# ProProject_20240809-UR5__2024-08-29.net
KiCad netlist of a schematic drawn in EasyEDA Pro
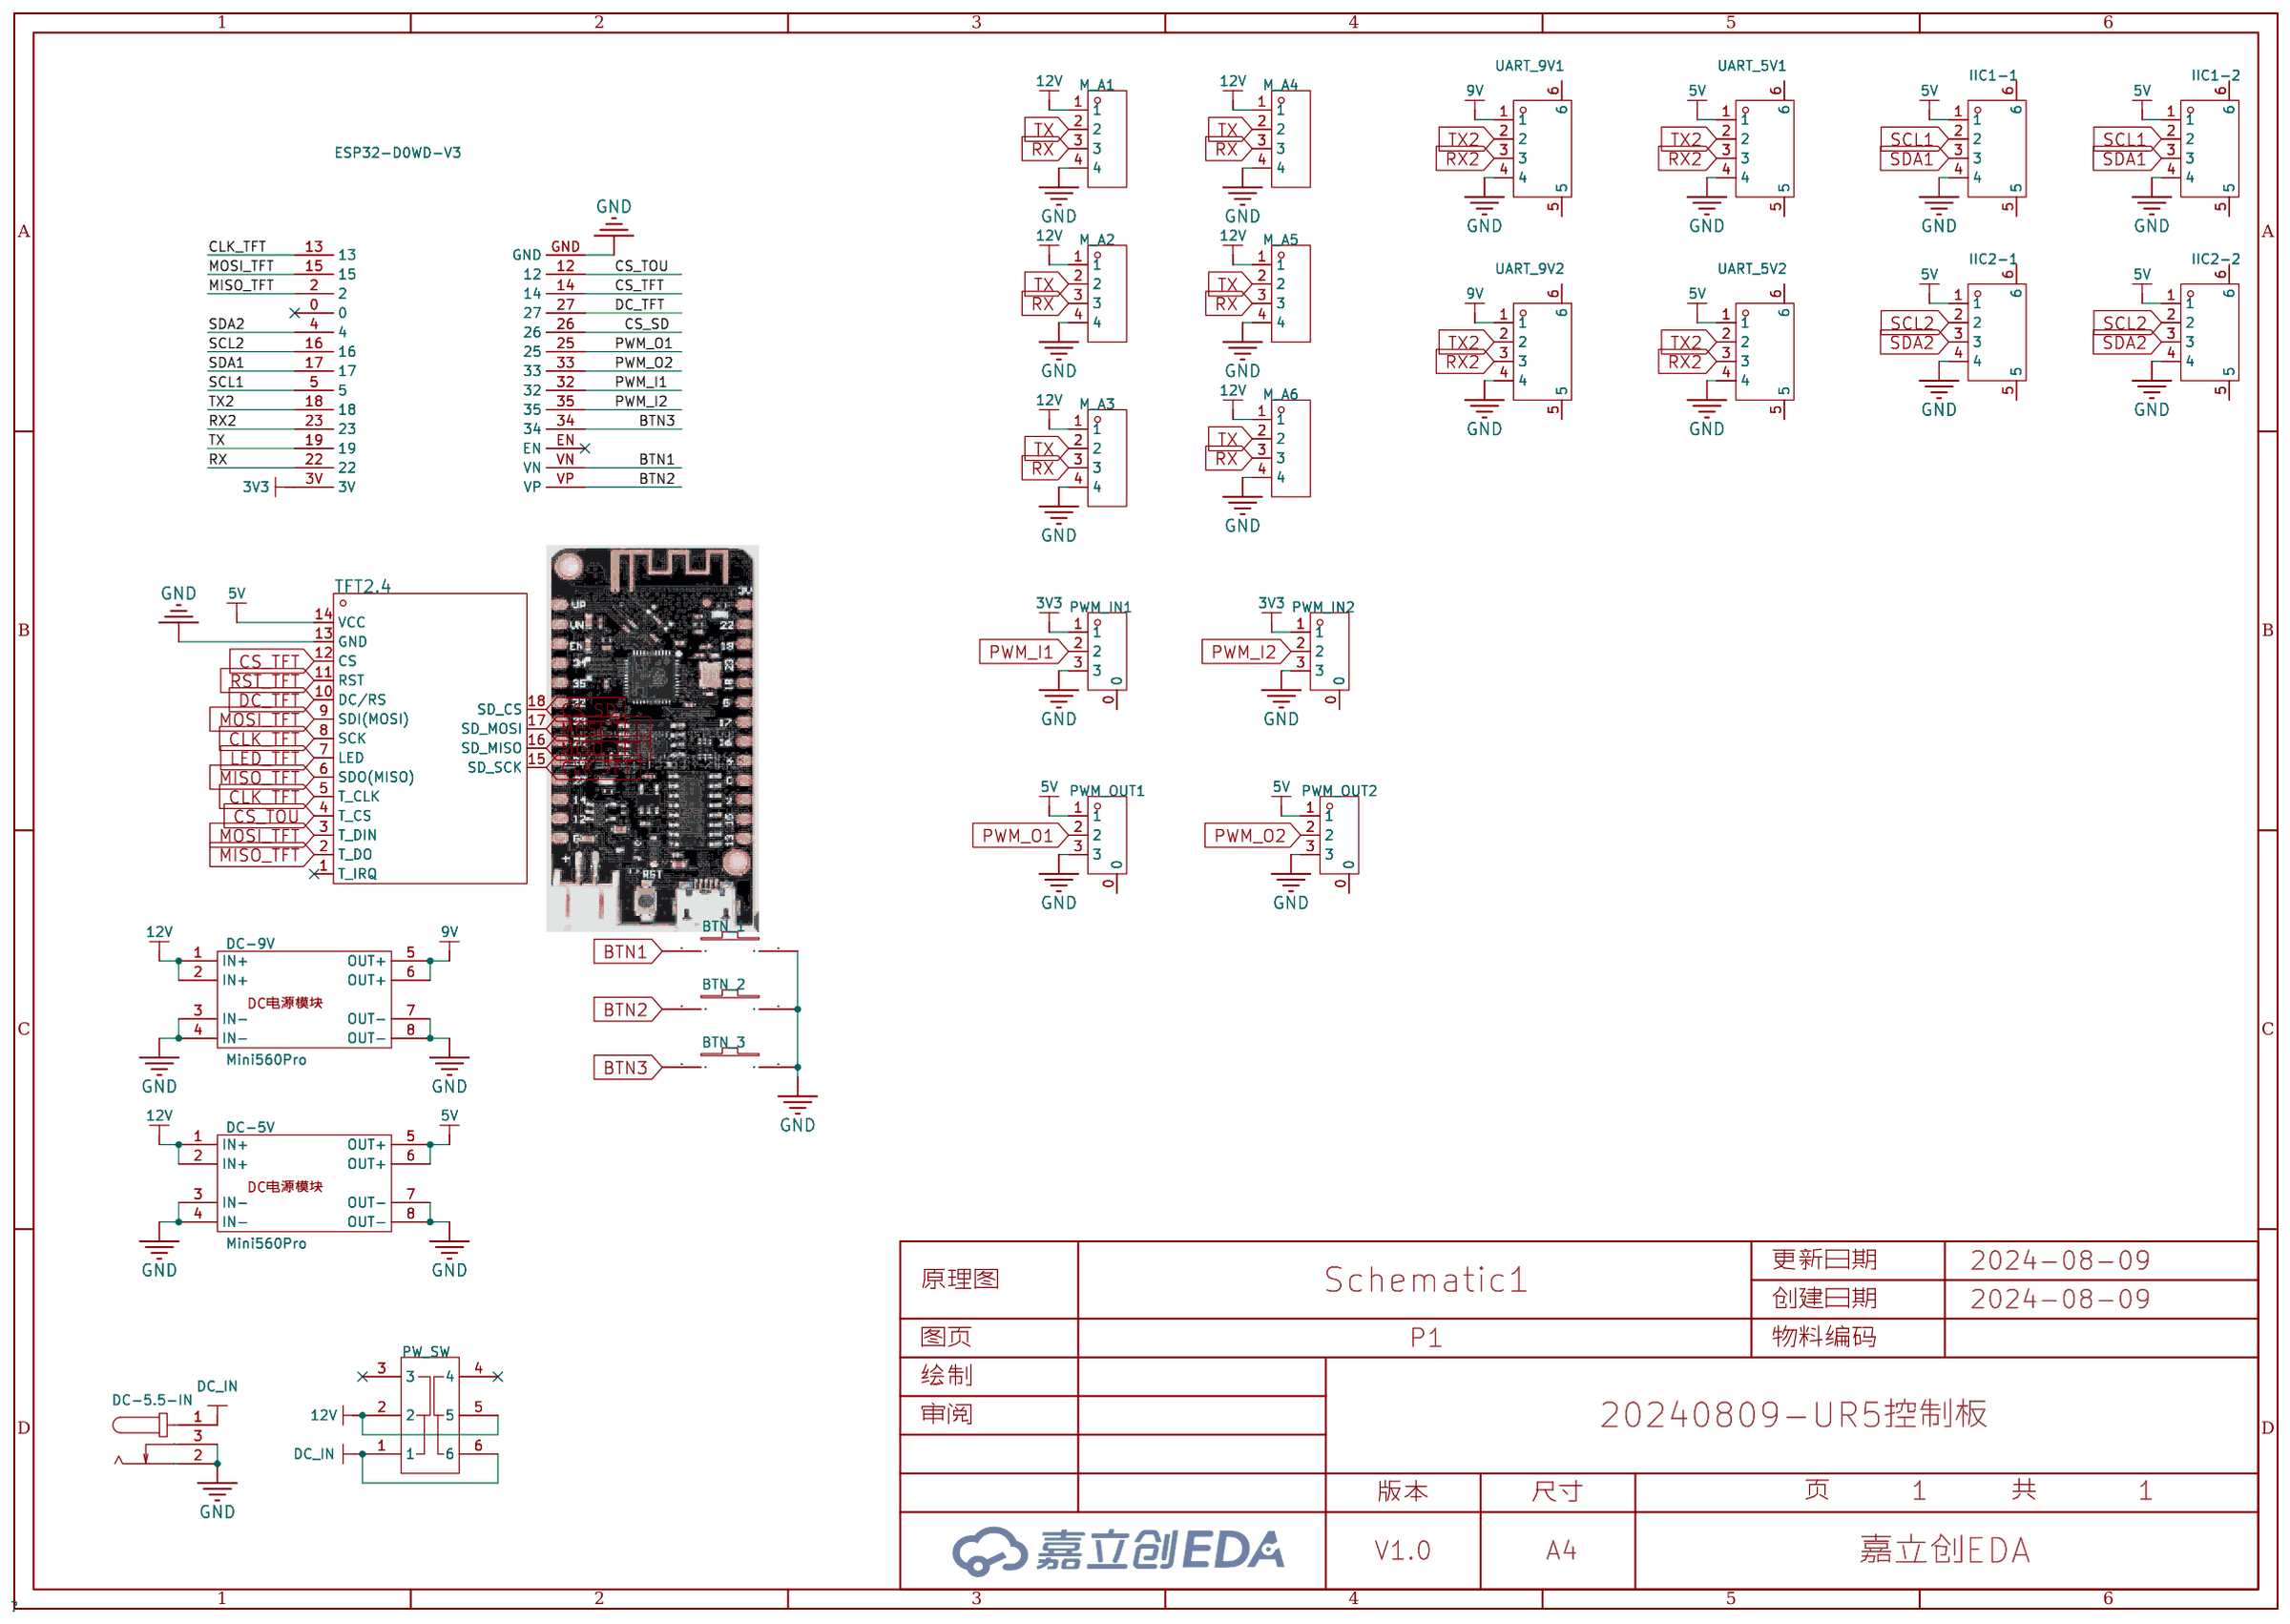
[diagram p0: schematic sheet]

(export (version "E")
  (design (tool "Eeschema 10.0.6"))
  (components
    (comp (ref "BTN_1")
      (value "K2-1104DZ-B4SW-04")
      (footprint "easyedapro:SW-TH_2P-L6.2-W6.2-P5.0")
      (description "作用力:250gf;安装方式:直插;开关长度:6mm;开关宽度:6mm;开关高度:4.5mm;触点电流:50mA;额定电压(DC):12V;绝缘电阻:100MΩ;机械寿命:10万次;")
      (fields (field (name "Manufacturer") "韩国韩荣"))
      (libsource (lib "easyedapro") (part "K2-1104DZ-B4SW-04"))
    )
    (comp (ref "BTN_2")
      (value "K2-1104DZ-B4SW-04")
      (footprint "easyedapro:SW-TH_2P-L6.2-W6.2-P5.0")
      (description "作用力:250gf;安装方式:直插;开关长度:6mm;开关宽度:6mm;开关高度:4.5mm;触点电流:50mA;额定电压(DC):12V;绝缘电阻:100MΩ;机械寿命:10万次;")
      (fields (field (name "Manufacturer") "韩国韩荣"))
      (libsource (lib "easyedapro") (part "K2-1104DZ-B4SW-04"))
    )
    (comp (ref "BTN_3")
      (value "K2-1104DZ-B4SW-04")
      (footprint "easyedapro:SW-TH_2P-L6.2-W6.2-P5.0")
      (description "作用力:250gf;安装方式:直插;开关长度:6mm;开关宽度:6mm;开关高度:4.5mm;触点电流:50mA;额定电压(DC):12V;绝缘电阻:100MΩ;机械寿命:10万次;")
      (fields (field (name "Manufacturer") "韩国韩荣"))
      (libsource (lib "easyedapro") (part "K2-1104DZ-B4SW-04"))
    )
    (comp (ref "DC-5.5-IN")
      (value "~")
      (footprint "easyedapro:DC母座")
      (libsource (lib "easyedapro") (part "DC母座"))
    )
    (comp (ref "DC-5V")
      (value "Mini560Pro")
      (footprint "easyedapro:Mini560Pro")
      (description "DC电源模块")
      (libsource (lib "easyedapro") (part "Mini560Pro"))
    )
    (comp (ref "DC-9V")
      (value "Mini560Pro")
      (footprint "easyedapro:Mini560Pro")
      (description "DC电源模块")
      (libsource (lib "easyedapro") (part "Mini560Pro"))
    )
    (comp (ref "ESP32-D0WD-V3")
      (value "~")
      (footprint "easyedapro:ESP32")
      (libsource (lib "easyedapro") (part "ESP32"))
    )
    (comp (ref "IIC1-1")
      (value "ZX-PH2.0-WT4P")
      (footprint "easyedapro:CONN-SMD_4P-P2.00_C2001RS10411M0101RC")
      (fields (field (name "Manufacturer") "Megastar(兆星)"))
      (libsource (lib "easyedapro") (part "ZX-PH2.0-WT4P"))
    )
    (comp (ref "IIC1-2")
      (value "ZX-PH2.0-WT4P")
      (footprint "easyedapro:CONN-SMD_4P-P2.00_C2001RS10411M0101RC")
      (fields (field (name "Manufacturer") "Megastar(兆星)"))
      (libsource (lib "easyedapro") (part "ZX-PH2.0-WT4P"))
    )
    (comp (ref "IIC2-1")
      (value "ZX-PH2.0-WT4P")
      (footprint "easyedapro:CONN-SMD_4P-P2.00_C2001RS10411M0101RC")
      (fields (field (name "Manufacturer") "Megastar(兆星)"))
      (libsource (lib "easyedapro") (part "ZX-PH2.0-WT4P"))
    )
    (comp (ref "IIC2-2")
      (value "ZX-PH2.0-WT4P")
      (footprint "easyedapro:CONN-SMD_4P-P2.00_C2001RS10411M0101RC")
      (fields (field (name "Manufacturer") "Megastar(兆星)"))
      (libsource (lib "easyedapro") (part "ZX-PH2.0-WT4P"))
    )
    (comp (ref "M_A1")
      (value "ZX-XH2.54-4PWZ")
      (footprint "easyedapro:CONN-TH_4P-P2.50_ZX-XH2.54-4PWZ")
      (fields (field (name "Manufacturer") "Megastar(兆星)"))
      (libsource (lib "easyedapro") (part "ZX-XH2.54-4PWZ"))
    )
    (comp (ref "M_A2")
      (value "ZX-XH2.54-4PWZ")
      (footprint "easyedapro:CONN-TH_4P-P2.50_ZX-XH2.54-4PWZ")
      (fields (field (name "Manufacturer") "Megastar(兆星)"))
      (libsource (lib "easyedapro") (part "ZX-XH2.54-4PWZ"))
    )
    (comp (ref "M_A3")
      (value "ZX-XH2.54-4PWZ")
      (footprint "easyedapro:CONN-TH_4P-P2.50_ZX-XH2.54-4PWZ")
      (fields (field (name "Manufacturer") "Megastar(兆星)"))
      (libsource (lib "easyedapro") (part "ZX-XH2.54-4PWZ"))
    )
    (comp (ref "M_A4")
      (value "ZX-XH2.54-4PWZ")
      (footprint "easyedapro:CONN-TH_4P-P2.50_ZX-XH2.54-4PWZ")
      (fields (field (name "Manufacturer") "Megastar(兆星)"))
      (libsource (lib "easyedapro") (part "ZX-XH2.54-4PWZ"))
    )
    (comp (ref "M_A5")
      (value "ZX-XH2.54-4PWZ")
      (footprint "easyedapro:CONN-TH_4P-P2.50_ZX-XH2.54-4PWZ")
      (fields (field (name "Manufacturer") "Megastar(兆星)"))
      (libsource (lib "easyedapro") (part "ZX-XH2.54-4PWZ"))
    )
    (comp (ref "M_A6")
      (value "ZX-XH2.54-4PWZ")
      (footprint "easyedapro:CONN-TH_4P-P2.50_ZX-XH2.54-4PWZ")
      (fields (field (name "Manufacturer") "Megastar(兆星)"))
      (libsource (lib "easyedapro") (part "ZX-XH2.54-4PWZ"))
    )
    (comp (ref "PWM_IN1")
      (value "SH1.0-3P")
      (footprint "easyedapro:CONN-SMD_3P-P1.00-L5.0-W5.0")
      (libsource (lib "easyedapro") (part "SH1.0-3P"))
    )
    (comp (ref "PWM_IN2")
      (value "SH1.0-3P")
      (footprint "easyedapro:CONN-SMD_3P-P1.00-L5.0-W5.0")
      (libsource (lib "easyedapro") (part "SH1.0-3P"))
    )
    (comp (ref "PWM_OUT1")
      (value "SH1.0-3P")
      (footprint "easyedapro:CONN-SMD_3P-P1.00-L5.0-W5.0")
      (libsource (lib "easyedapro") (part "SH1.0-3P"))
    )
    (comp (ref "PWM_OUT2")
      (value "SH1.0-3P")
      (footprint "easyedapro:CONN-SMD_3P-P1.00-L5.0-W5.0")
      (libsource (lib "easyedapro") (part "SH1.0-3P"))
    )
    (comp (ref "PW_SW")
      (value "开关-9*3.5")
      (footprint "easyedapro:SK09C G2")
      (libsource (lib "easyedapro") (part "SK09C G2"))
    )
    (comp (ref "TFT2.4")
      (value "~")
      (footprint "easyedapro:TFT_2.4_18P_SPI_ILI9341_240X320_65K_S_1")
      (description "2.4寸SPI串口液晶屏TFT彩屏ILI9341驱动")
      (libsource (lib "easyedapro") (part "TFT_2.4_18P_SPI_ILI9341_240X320_65K_S_1"))
    )
    (comp (ref "UART_5V1")
      (value "ZX-PH2.0-WT4P")
      (footprint "easyedapro:CONN-SMD_4P-P2.00_C2001RS10411M0101RC")
      (fields (field (name "Manufacturer") "Megastar(兆星)"))
      (libsource (lib "easyedapro") (part "ZX-PH2.0-WT4P"))
    )
    (comp (ref "UART_5V2")
      (value "ZX-PH2.0-WT4P")
      (footprint "easyedapro:CONN-SMD_4P-P2.00_C2001RS10411M0101RC")
      (fields (field (name "Manufacturer") "Megastar(兆星)"))
      (libsource (lib "easyedapro") (part "ZX-PH2.0-WT4P"))
    )
    (comp (ref "UART_9V1")
      (value "ZX-PH2.0-WT4P")
      (footprint "easyedapro:CONN-SMD_4P-P2.00_C2001RS10411M0101RC")
      (fields (field (name "Manufacturer") "Megastar(兆星)"))
      (libsource (lib "easyedapro") (part "ZX-PH2.0-WT4P"))
    )
    (comp (ref "UART_9V2")
      (value "ZX-PH2.0-WT4P")
      (footprint "easyedapro:CONN-SMD_4P-P2.00_C2001RS10411M0101RC")
      (fields (field (name "Manufacturer") "Megastar(兆星)"))
      (libsource (lib "easyedapro") (part "ZX-PH2.0-WT4P"))
    )
  )
  (nets
    (net (code "1") (name "3V3") (class "Default")
      (node (ref "ESP32-D0WD-V3") (pin "3V") (pinfunction "3V_3V") (pintype "input"))
      (node (ref "PWM_IN1") (pin "1") (pinfunction "1_1") (pintype "unspecified"))
      (node (ref "PWM_IN2") (pin "1") (pinfunction "1_1") (pintype "unspecified"))
    )
    (net (code "2") (name "5V") (class "Default")
      (node (ref "DC-5V") (pin "5") (pinfunction "OUT+_5") (pintype "input"))
      (node (ref "DC-5V") (pin "6") (pinfunction "OUT+_6") (pintype "input"))
      (node (ref "IIC1-1") (pin "1") (pinfunction "1_1") (pintype "unspecified"))
      (node (ref "IIC1-2") (pin "1") (pinfunction "1_1") (pintype "unspecified"))
      (node (ref "IIC2-1") (pin "1") (pinfunction "1_1") (pintype "unspecified"))
      (node (ref "IIC2-2") (pin "1") (pinfunction "1_1") (pintype "unspecified"))
      (node (ref "PWM_OUT1") (pin "1") (pinfunction "1_1") (pintype "unspecified"))
      (node (ref "PWM_OUT2") (pin "1") (pinfunction "1_1") (pintype "unspecified"))
      (node (ref "TFT2.4") (pin "14") (pinfunction "VCC_14") (pintype "unspecified"))
      (node (ref "UART_5V1") (pin "1") (pinfunction "1_1") (pintype "unspecified"))
      (node (ref "UART_5V2") (pin "1") (pinfunction "1_1") (pintype "unspecified"))
    )
    (net (code "3") (name "9V") (class "Default")
      (node (ref "DC-9V") (pin "5") (pinfunction "OUT+_5") (pintype "input"))
      (node (ref "DC-9V") (pin "6") (pinfunction "OUT+_6") (pintype "input"))
      (node (ref "UART_9V1") (pin "1") (pinfunction "1_1") (pintype "unspecified"))
      (node (ref "UART_9V2") (pin "1") (pinfunction "1_1") (pintype "unspecified"))
    )
    (net (code "4") (name "12V") (class "Default")
      (node (ref "DC-5V") (pin "1") (pinfunction "IN+_1") (pintype "input"))
      (node (ref "DC-5V") (pin "2") (pinfunction "IN+_2") (pintype "input"))
      (node (ref "DC-9V") (pin "1") (pinfunction "IN+_1") (pintype "input"))
      (node (ref "DC-9V") (pin "2") (pinfunction "IN+_2") (pintype "input"))
      (node (ref "M_A1") (pin "1") (pinfunction "1_1") (pintype "unspecified"))
      (node (ref "M_A2") (pin "1") (pinfunction "1_1") (pintype "unspecified"))
      (node (ref "M_A3") (pin "1") (pinfunction "1_1") (pintype "unspecified"))
      (node (ref "M_A4") (pin "1") (pinfunction "1_1") (pintype "unspecified"))
      (node (ref "M_A5") (pin "1") (pinfunction "1_1") (pintype "unspecified"))
      (node (ref "M_A6") (pin "1") (pinfunction "1_1") (pintype "unspecified"))
      (node (ref "PW_SW") (pin "2") (pinfunction "2_2") (pintype "input"))
      (node (ref "PW_SW") (pin "5") (pinfunction "5_5") (pintype "input"))
    )
    (net (code "5") (name "BTN1") (class "Default")
      (node (ref "BTN_1") (pin "1") (pinfunction "1_1") (pintype "input"))
      (node (ref "ESP32-D0WD-V3") (pin "VN") (pinfunction "VN_VN") (pintype "input"))
    )
    (net (code "6") (name "BTN2") (class "Default")
      (node (ref "BTN_2") (pin "1") (pinfunction "1_1") (pintype "input"))
      (node (ref "ESP32-D0WD-V3") (pin "VP") (pinfunction "VP_VP") (pintype "input"))
    )
    (net (code "7") (name "BTN3") (class "Default")
      (node (ref "BTN_3") (pin "1") (pinfunction "1_1") (pintype "input"))
      (node (ref "ESP32-D0WD-V3") (pin "34") (pinfunction "34_34") (pintype "input"))
    )
    (net (code "8") (name "CLK_TFT") (class "Default")
      (node (ref "ESP32-D0WD-V3") (pin "13") (pinfunction "13_13") (pintype "input"))
      (node (ref "TFT2.4") (pin "15") (pinfunction "SD_SCK_15") (pintype "unspecified"))
      (node (ref "TFT2.4") (pin "5") (pinfunction "T_CLK_5") (pintype "unspecified"))
      (node (ref "TFT2.4") (pin "8") (pinfunction "SCK_8") (pintype "unspecified"))
    )
    (net (code "9") (name "CS_SD") (class "Default")
      (node (ref "ESP32-D0WD-V3") (pin "26") (pinfunction "26_26") (pintype "input"))
      (node (ref "TFT2.4") (pin "18") (pinfunction "SD_CS_18") (pintype "unspecified"))
    )
    (net (code "10") (name "CS_TFT") (class "Default")
      (node (ref "ESP32-D0WD-V3") (pin "14") (pinfunction "14_14") (pintype "input"))
      (node (ref "TFT2.4") (pin "12") (pinfunction "CS_12") (pintype "unspecified"))
    )
    (net (code "11") (name "CS_TOU") (class "Default")
      (node (ref "ESP32-D0WD-V3") (pin "12") (pinfunction "12_12") (pintype "input"))
      (node (ref "TFT2.4") (pin "4") (pinfunction "T_CS_4") (pintype "unspecified"))
    )
    (net (code "12") (name "DC_IN") (class "Default")
      (node (ref "DC-5.5-IN") (pin "1") (pinfunction "1_1") (pintype "input"))
      (node (ref "PW_SW") (pin "1") (pinfunction "1_1") (pintype "input"))
      (node (ref "PW_SW") (pin "6") (pinfunction "6_6") (pintype "input"))
    )
    (net (code "13") (name "DC_TFT") (class "Default")
      (node (ref "ESP32-D0WD-V3") (pin "27") (pinfunction "27_27") (pintype "input"))
      (node (ref "TFT2.4") (pin "10") (pinfunction "DC/RS_10") (pintype "unspecified"))
    )
    (net (code "14") (name "GND") (class "Default")
      (node (ref "BTN_1") (pin "2") (pinfunction "2_2") (pintype "input"))
      (node (ref "BTN_2") (pin "2") (pinfunction "2_2") (pintype "input"))
      (node (ref "BTN_3") (pin "2") (pinfunction "2_2") (pintype "input"))
      (node (ref "DC-5.5-IN") (pin "2") (pinfunction "2_2") (pintype "input"))
      (node (ref "DC-5.5-IN") (pin "3") (pinfunction "3_3") (pintype "input"))
      (node (ref "DC-5V") (pin "3") (pinfunction "IN-_3") (pintype "input"))
      (node (ref "DC-5V") (pin "4") (pinfunction "IN-_4") (pintype "input"))
      (node (ref "DC-5V") (pin "7") (pinfunction "OUT-_7") (pintype "input"))
      (node (ref "DC-5V") (pin "8") (pinfunction "OUT-_8") (pintype "input"))
      (node (ref "DC-9V") (pin "3") (pinfunction "IN-_3") (pintype "input"))
      (node (ref "DC-9V") (pin "4") (pinfunction "IN-_4") (pintype "input"))
      (node (ref "DC-9V") (pin "7") (pinfunction "OUT-_7") (pintype "input"))
      (node (ref "DC-9V") (pin "8") (pinfunction "OUT-_8") (pintype "input"))
      (node (ref "ESP32-D0WD-V3") (pin "GND") (pinfunction "GND_GND") (pintype "input"))
      (node (ref "IIC1-1") (pin "4") (pinfunction "4_4") (pintype "unspecified"))
      (node (ref "IIC1-2") (pin "4") (pinfunction "4_4") (pintype "unspecified"))
      (node (ref "IIC2-1") (pin "4") (pinfunction "4_4") (pintype "unspecified"))
      (node (ref "IIC2-2") (pin "4") (pinfunction "4_4") (pintype "unspecified"))
      (node (ref "M_A1") (pin "4") (pinfunction "4_4") (pintype "unspecified"))
      (node (ref "M_A2") (pin "4") (pinfunction "4_4") (pintype "unspecified"))
      (node (ref "M_A3") (pin "4") (pinfunction "4_4") (pintype "unspecified"))
      (node (ref "M_A4") (pin "4") (pinfunction "4_4") (pintype "unspecified"))
      (node (ref "M_A5") (pin "4") (pinfunction "4_4") (pintype "unspecified"))
      (node (ref "M_A6") (pin "4") (pinfunction "4_4") (pintype "unspecified"))
      (node (ref "PWM_IN1") (pin "3") (pinfunction "3_3") (pintype "unspecified"))
      (node (ref "PWM_IN2") (pin "3") (pinfunction "3_3") (pintype "unspecified"))
      (node (ref "PWM_OUT1") (pin "3") (pinfunction "3_3") (pintype "unspecified"))
      (node (ref "PWM_OUT2") (pin "3") (pinfunction "3_3") (pintype "unspecified"))
      (node (ref "TFT2.4") (pin "13") (pinfunction "GND_13") (pintype "unspecified"))
      (node (ref "UART_5V1") (pin "4") (pinfunction "4_4") (pintype "unspecified"))
      (node (ref "UART_5V2") (pin "4") (pinfunction "4_4") (pintype "unspecified"))
      (node (ref "UART_9V1") (pin "4") (pinfunction "4_4") (pintype "unspecified"))
      (node (ref "UART_9V2") (pin "4") (pinfunction "4_4") (pintype "unspecified"))
    )
    (net (code "15") (name "LED_TFT") (class "Default")
      (node (ref "TFT2.4") (pin "7") (pinfunction "LED_7") (pintype "unspecified"))
    )
    (net (code "16") (name "MISO_TFT") (class "Default")
      (node (ref "ESP32-D0WD-V3") (pin "2") (pinfunction "2_2") (pintype "input"))
      (node (ref "TFT2.4") (pin "16") (pinfunction "SD_MISO_16") (pintype "unspecified"))
      (node (ref "TFT2.4") (pin "2") (pinfunction "T_DO_2") (pintype "unspecified"))
      (node (ref "TFT2.4") (pin "6") (pinfunction "SDO(MISO)_6") (pintype "unspecified"))
    )
    (net (code "17") (name "MOSI_TFT") (class "Default")
      (node (ref "ESP32-D0WD-V3") (pin "15") (pinfunction "15_15") (pintype "input"))
      (node (ref "TFT2.4") (pin "17") (pinfunction "SD_MOSI_17") (pintype "unspecified"))
      (node (ref "TFT2.4") (pin "3") (pinfunction "T_DIN_3") (pintype "unspecified"))
      (node (ref "TFT2.4") (pin "9") (pinfunction "SDI(MOSI)_9") (pintype "unspecified"))
    )
    (net (code "18") (name "PWM_I1") (class "Default")
      (node (ref "ESP32-D0WD-V3") (pin "32") (pinfunction "32_32") (pintype "input"))
      (node (ref "PWM_IN1") (pin "2") (pinfunction "2_2") (pintype "unspecified"))
    )
    (net (code "19") (name "PWM_I2") (class "Default")
      (node (ref "ESP32-D0WD-V3") (pin "35") (pinfunction "35_35") (pintype "input"))
      (node (ref "PWM_IN2") (pin "2") (pinfunction "2_2") (pintype "unspecified"))
    )
    (net (code "20") (name "PWM_O1") (class "Default")
      (node (ref "ESP32-D0WD-V3") (pin "25") (pinfunction "25_25") (pintype "input"))
      (node (ref "PWM_OUT1") (pin "2") (pinfunction "2_2") (pintype "unspecified"))
    )
    (net (code "21") (name "PWM_O2") (class "Default")
      (node (ref "ESP32-D0WD-V3") (pin "33") (pinfunction "33_33") (pintype "input"))
      (node (ref "PWM_OUT2") (pin "2") (pinfunction "2_2") (pintype "unspecified"))
    )
    (net (code "22") (name "RST_TFT") (class "Default")
      (node (ref "TFT2.4") (pin "11") (pinfunction "RST_11") (pintype "unspecified"))
    )
    (net (code "23") (name "RX") (class "Default")
      (node (ref "ESP32-D0WD-V3") (pin "22") (pinfunction "22_22") (pintype "input"))
      (node (ref "M_A1") (pin "3") (pinfunction "3_3") (pintype "unspecified"))
      (node (ref "M_A2") (pin "3") (pinfunction "3_3") (pintype "unspecified"))
      (node (ref "M_A3") (pin "3") (pinfunction "3_3") (pintype "unspecified"))
      (node (ref "M_A4") (pin "3") (pinfunction "3_3") (pintype "unspecified"))
      (node (ref "M_A5") (pin "3") (pinfunction "3_3") (pintype "unspecified"))
      (node (ref "M_A6") (pin "3") (pinfunction "3_3") (pintype "unspecified"))
    )
    (net (code "24") (name "RX2") (class "Default")
      (node (ref "ESP32-D0WD-V3") (pin "23") (pinfunction "23_23") (pintype "input"))
      (node (ref "UART_5V1") (pin "3") (pinfunction "3_3") (pintype "unspecified"))
      (node (ref "UART_5V2") (pin "3") (pinfunction "3_3") (pintype "unspecified"))
      (node (ref "UART_9V1") (pin "3") (pinfunction "3_3") (pintype "unspecified"))
      (node (ref "UART_9V2") (pin "3") (pinfunction "3_3") (pintype "unspecified"))
    )
    (net (code "25") (name "SCL1") (class "Default")
      (node (ref "ESP32-D0WD-V3") (pin "5") (pinfunction "5_5") (pintype "input"))
      (node (ref "IIC1-1") (pin "2") (pinfunction "2_2") (pintype "unspecified"))
      (node (ref "IIC1-2") (pin "2") (pinfunction "2_2") (pintype "unspecified"))
    )
    (net (code "26") (name "SCL2") (class "Default")
      (node (ref "ESP32-D0WD-V3") (pin "16") (pinfunction "16_16") (pintype "input"))
      (node (ref "IIC2-1") (pin "2") (pinfunction "2_2") (pintype "unspecified"))
      (node (ref "IIC2-2") (pin "2") (pinfunction "2_2") (pintype "unspecified"))
    )
    (net (code "27") (name "SDA1") (class "Default")
      (node (ref "ESP32-D0WD-V3") (pin "17") (pinfunction "17_17") (pintype "input"))
      (node (ref "IIC1-1") (pin "3") (pinfunction "3_3") (pintype "unspecified"))
      (node (ref "IIC1-2") (pin "3") (pinfunction "3_3") (pintype "unspecified"))
    )
    (net (code "28") (name "SDA2") (class "Default")
      (node (ref "ESP32-D0WD-V3") (pin "4") (pinfunction "4_4") (pintype "input"))
      (node (ref "IIC2-1") (pin "3") (pinfunction "3_3") (pintype "unspecified"))
      (node (ref "IIC2-2") (pin "3") (pinfunction "3_3") (pintype "unspecified"))
    )
    (net (code "29") (name "TX") (class "Default")
      (node (ref "ESP32-D0WD-V3") (pin "19") (pinfunction "19_19") (pintype "input"))
      (node (ref "M_A1") (pin "2") (pinfunction "2_2") (pintype "unspecified"))
      (node (ref "M_A2") (pin "2") (pinfunction "2_2") (pintype "unspecified"))
      (node (ref "M_A3") (pin "2") (pinfunction "2_2") (pintype "unspecified"))
      (node (ref "M_A4") (pin "2") (pinfunction "2_2") (pintype "unspecified"))
      (node (ref "M_A5") (pin "2") (pinfunction "2_2") (pintype "unspecified"))
      (node (ref "M_A6") (pin "2") (pinfunction "2_2") (pintype "unspecified"))
    )
    (net (code "30") (name "TX2") (class "Default")
      (node (ref "ESP32-D0WD-V3") (pin "18") (pinfunction "18_18") (pintype "input"))
      (node (ref "UART_5V1") (pin "2") (pinfunction "2_2") (pintype "unspecified"))
      (node (ref "UART_5V2") (pin "2") (pinfunction "2_2") (pintype "unspecified"))
      (node (ref "UART_9V1") (pin "2") (pinfunction "2_2") (pintype "unspecified"))
      (node (ref "UART_9V2") (pin "2") (pinfunction "2_2") (pintype "unspecified"))
    )
    (net (code "31") (name "unconnected-(ESP32-D0WD-V3-Pad0)") (class "Default")
      (node (ref "ESP32-D0WD-V3") (pin "0") (pinfunction "0_0") (pintype "input+no_connect"))
    )
    (net (code "32") (name "unconnected-(ESP32-D0WD-V3-PadEN)") (class "Default")
      (node (ref "ESP32-D0WD-V3") (pin "EN") (pinfunction "EN_EN") (pintype "input+no_connect"))
    )
    (net (code "33") (name "unconnected-(IIC1-1-Pad5)") (class "Default")
      (node (ref "IIC1-1") (pin "5") (pinfunction "5_5") (pintype "unspecified"))
    )
    (net (code "34") (name "unconnected-(IIC1-1-Pad6)") (class "Default")
      (node (ref "IIC1-1") (pin "6") (pinfunction "6_6") (pintype "unspecified"))
    )
    (net (code "35") (name "unconnected-(IIC1-2-Pad5)") (class "Default")
      (node (ref "IIC1-2") (pin "5") (pinfunction "5_5") (pintype "unspecified"))
    )
    (net (code "36") (name "unconnected-(IIC1-2-Pad6)") (class "Default")
      (node (ref "IIC1-2") (pin "6") (pinfunction "6_6") (pintype "unspecified"))
    )
    (net (code "37") (name "unconnected-(IIC2-1-Pad5)") (class "Default")
      (node (ref "IIC2-1") (pin "5") (pinfunction "5_5") (pintype "unspecified"))
    )
    (net (code "38") (name "unconnected-(IIC2-1-Pad6)") (class "Default")
      (node (ref "IIC2-1") (pin "6") (pinfunction "6_6") (pintype "unspecified"))
    )
    (net (code "39") (name "unconnected-(IIC2-2-Pad5)") (class "Default")
      (node (ref "IIC2-2") (pin "5") (pinfunction "5_5") (pintype "unspecified"))
    )
    (net (code "40") (name "unconnected-(IIC2-2-Pad6)") (class "Default")
      (node (ref "IIC2-2") (pin "6") (pinfunction "6_6") (pintype "unspecified"))
    )
    (net (code "41") (name "unconnected-(PWM_IN1-Pad0)") (class "Default")
      (node (ref "PWM_IN1") (pin "0") (pinfunction "0_0") (pintype "unspecified"))
    )
    (net (code "42") (name "unconnected-(PWM_IN2-Pad0)") (class "Default")
      (node (ref "PWM_IN2") (pin "0") (pinfunction "0_0") (pintype "unspecified"))
    )
    (net (code "43") (name "unconnected-(PWM_OUT1-Pad0)") (class "Default")
      (node (ref "PWM_OUT1") (pin "0") (pinfunction "0_0") (pintype "unspecified"))
    )
    (net (code "44") (name "unconnected-(PWM_OUT2-Pad0)") (class "Default")
      (node (ref "PWM_OUT2") (pin "0") (pinfunction "0_0") (pintype "unspecified"))
    )
    (net (code "45") (name "unconnected-(PW_SW-Pad3)") (class "Default")
      (node (ref "PW_SW") (pin "3") (pinfunction "3_3") (pintype "input+no_connect"))
    )
    (net (code "46") (name "unconnected-(PW_SW-Pad4)") (class "Default")
      (node (ref "PW_SW") (pin "4") (pinfunction "4_4") (pintype "input+no_connect"))
    )
    (net (code "47") (name "unconnected-(TFT2.4-T_IRQ-Pad1)") (class "Default")
      (node (ref "TFT2.4") (pin "1") (pinfunction "T_IRQ_1") (pintype "unspecified+no_connect"))
    )
    (net (code "48") (name "unconnected-(UART_5V1-Pad5)") (class "Default")
      (node (ref "UART_5V1") (pin "5") (pinfunction "5_5") (pintype "unspecified"))
    )
    (net (code "49") (name "unconnected-(UART_5V1-Pad6)") (class "Default")
      (node (ref "UART_5V1") (pin "6") (pinfunction "6_6") (pintype "unspecified"))
    )
    (net (code "50") (name "unconnected-(UART_5V2-Pad5)") (class "Default")
      (node (ref "UART_5V2") (pin "5") (pinfunction "5_5") (pintype "unspecified"))
    )
    (net (code "51") (name "unconnected-(UART_5V2-Pad6)") (class "Default")
      (node (ref "UART_5V2") (pin "6") (pinfunction "6_6") (pintype "unspecified"))
    )
    (net (code "52") (name "unconnected-(UART_9V1-Pad5)") (class "Default")
      (node (ref "UART_9V1") (pin "5") (pinfunction "5_5") (pintype "unspecified"))
    )
    (net (code "53") (name "unconnected-(UART_9V1-Pad6)") (class "Default")
      (node (ref "UART_9V1") (pin "6") (pinfunction "6_6") (pintype "unspecified"))
    )
    (net (code "54") (name "unconnected-(UART_9V2-Pad5)") (class "Default")
      (node (ref "UART_9V2") (pin "5") (pinfunction "5_5") (pintype "unspecified"))
    )
    (net (code "55") (name "unconnected-(UART_9V2-Pad6)") (class "Default")
      (node (ref "UART_9V2") (pin "6") (pinfunction "6_6") (pintype "unspecified"))
    )
  )
)
